# Ant_Robot.net
KiCad netlist of a schematic drawn in Altium Designer
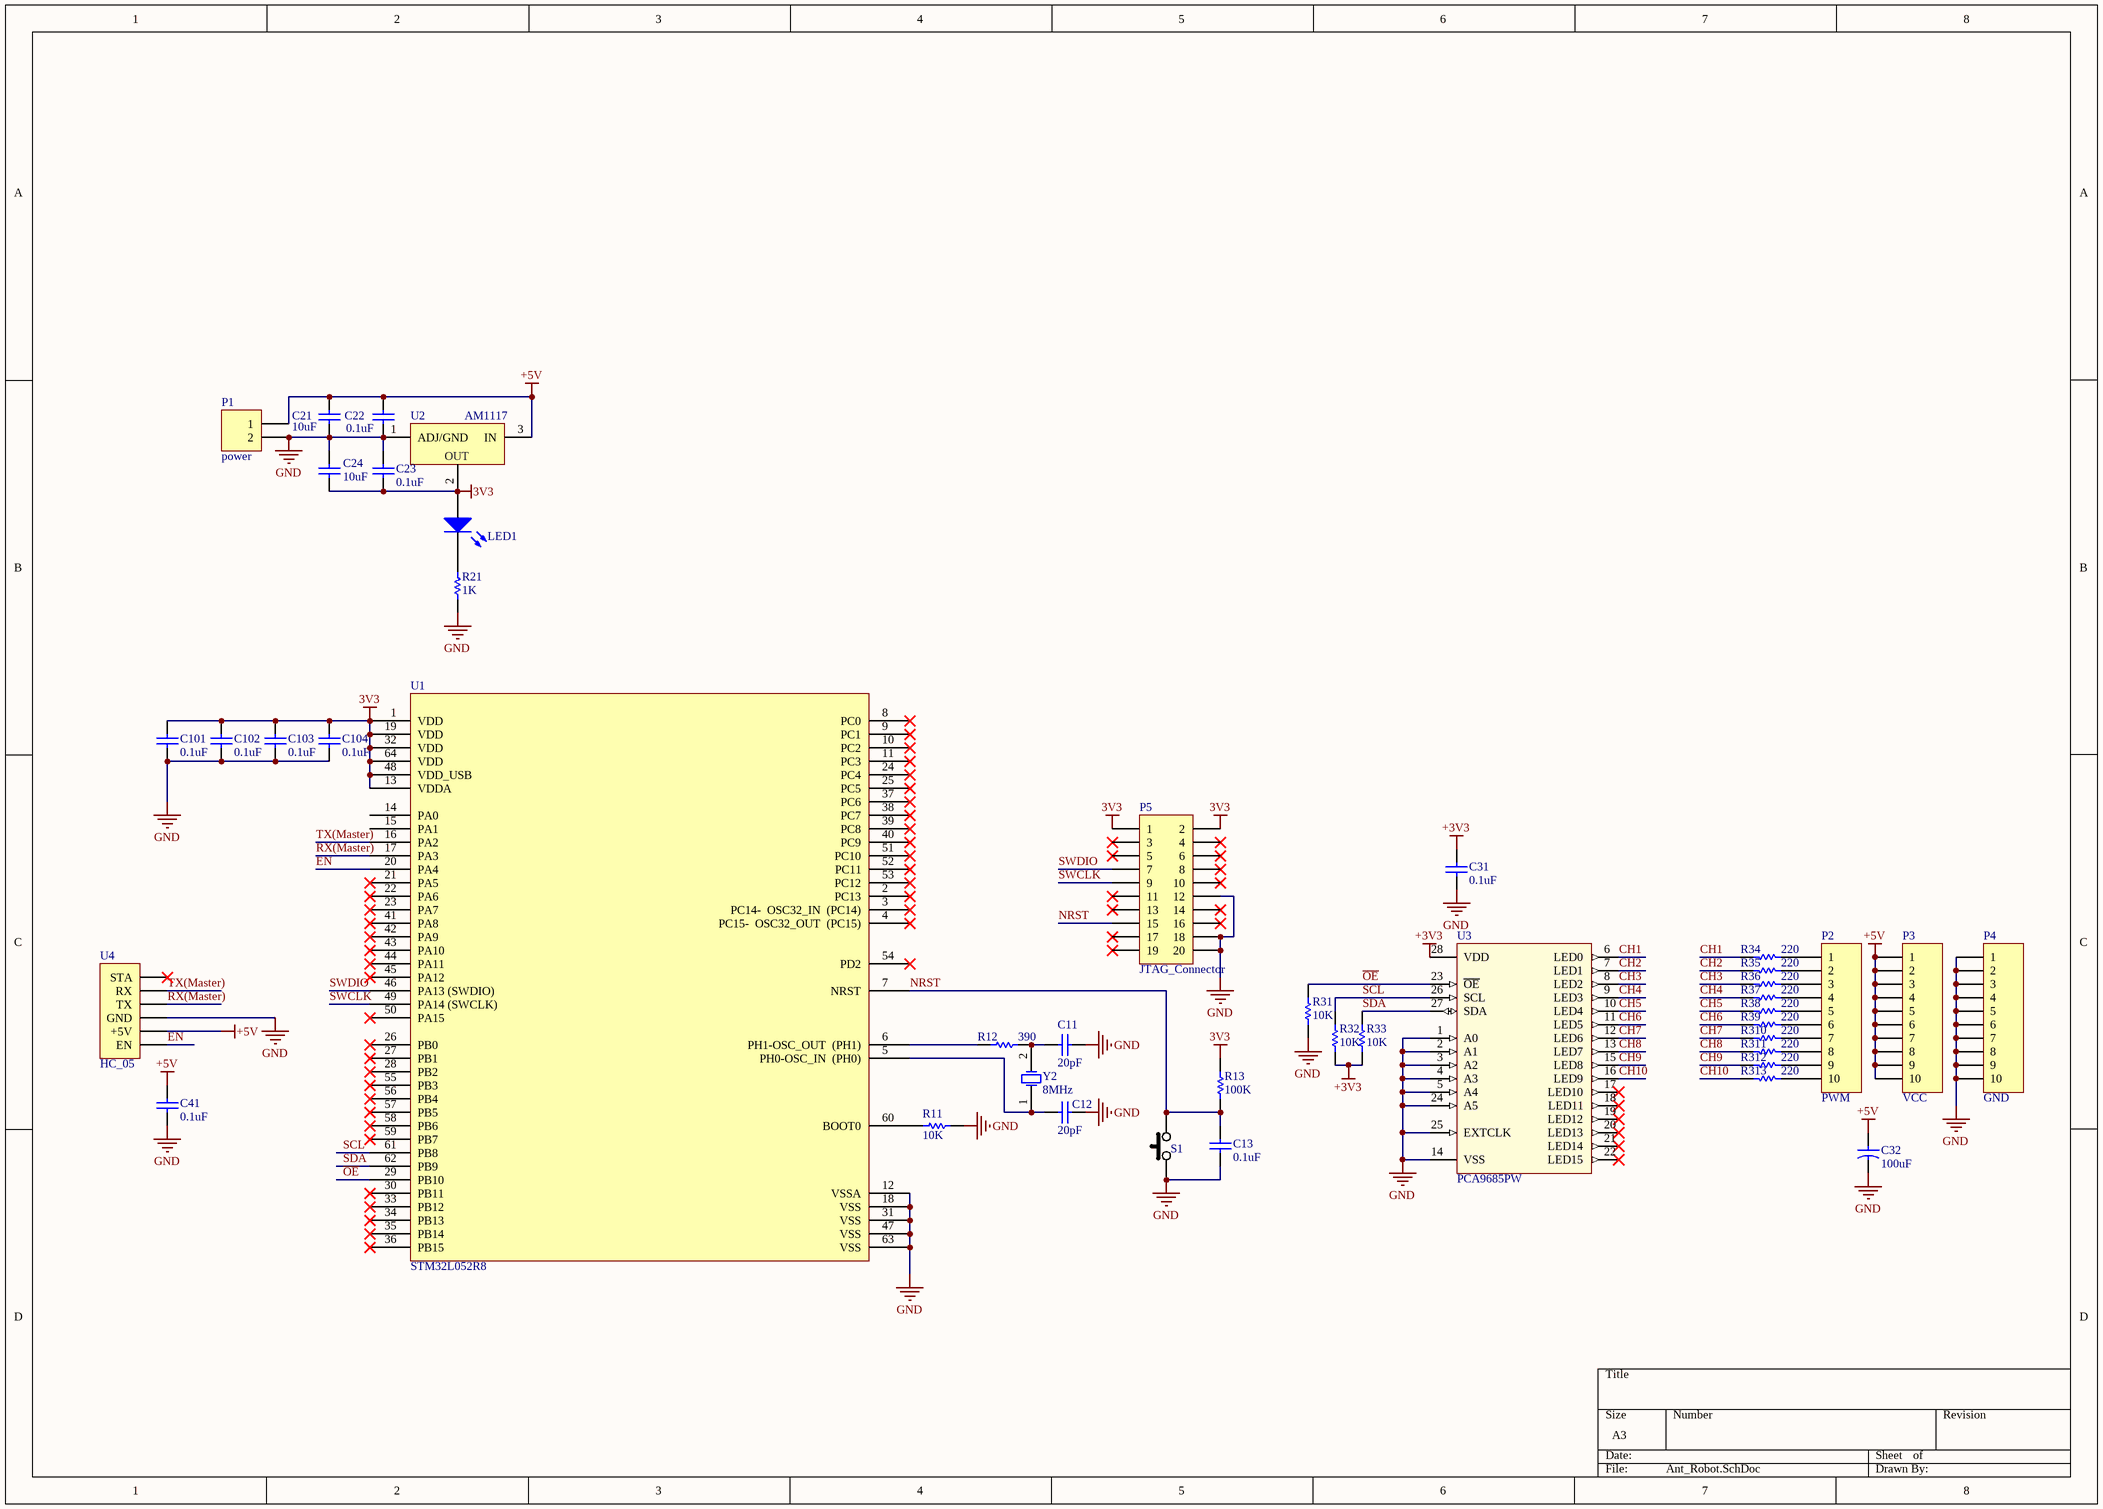
[diagram p0: Ant_Robot.SchDoc]

(export (version "E")
  (design (tool "Eeschema 10.0.6"))
  (components
    (comp (ref "C11") (value "20pF") (footprint "SMD 0805") (libsource (lib "零件庫") (part "C1 陶瓷")))
    (comp (ref "C12") (value "20pF") (footprint "SMD 0805") (libsource (lib "零件庫") (part "C1 陶瓷")))
    (comp (ref "C13") (value "0.1uF") (footprint "SMD 0805") (libsource (lib "零件庫") (part "C1 陶瓷")))
    (comp (ref "C21") (value "10uF") (footprint "SMD 0805") (libsource (lib "零件庫") (part "C1 陶瓷")))
    (comp (ref "C22") (value "0.1uF") (footprint "SMD 0805") (libsource (lib "零件庫") (part "C1 陶瓷")))
    (comp (ref "C23") (value "0.1uF") (footprint "SMD 0805") (libsource (lib "零件庫") (part "C1 陶瓷")))
    (comp (ref "C24") (value "10uF") (footprint "SMD 0805") (libsource (lib "零件庫") (part "C1 陶瓷")))
    (comp (ref "C31") (value "0.1uF") (footprint "SMD 0805") (libsource (lib "零件庫") (part "C1 陶瓷")))
    (comp (ref "C32") (value "100uF") (footprint "C2") (libsource (lib "零件庫") (part "C2 電解")))
    (comp (ref "C41") (value "0.1uF") (footprint "SMD 0805") (libsource (lib "零件庫") (part "C1 陶瓷")))
    (comp (ref "C101") (value "0.1uF") (footprint "SMD 0805") (libsource (lib "零件庫") (part "C1 陶瓷")))
    (comp (ref "C102") (value "0.1uF") (footprint "SMD 0805") (libsource (lib "零件庫") (part "C1 陶瓷")))
    (comp (ref "C103") (value "0.1uF") (footprint "SMD 0805") (libsource (lib "零件庫") (part "C1 陶瓷")))
    (comp (ref "C104") (value "0.1uF") (footprint "SMD 0805") (libsource (lib "零件庫") (part "C1 陶瓷")))
    (comp (ref "LED1") (value "LED") (footprint "SMD 0805") (libsource (lib "零件庫") (part "LED")))
    (comp (ref "P1")
      (value "power")
      (footprint "HDR1X2 - 5mm")
      (description "Header, 2-Pin")
      (fields (field (name "PUBLISHER") "Altium Limited"))
      (libsource (lib "零件庫") (part "Header 2"))
    )
    (comp (ref "P2")
      (value "PWM")
      (footprint "HDR1X10")
      (description "Header, 10-Pin")
      (fields (field (name "PUBLISHER") "Altium Limited"))
      (libsource (lib "Miscellaneous Connectors") (part "Header 10"))
    )
    (comp (ref "P3")
      (value "VCC")
      (footprint "HDR1X10")
      (description "Header, 10-Pin")
      (fields (field (name "PUBLISHER") "Altium Limited"))
      (libsource (lib "Miscellaneous Connectors") (part "Header 10"))
    )
    (comp (ref "P4")
      (value "GND")
      (footprint "HDR1X10")
      (description "Header, 10-Pin")
      (fields (field (name "PUBLISHER") "Altium Limited"))
      (libsource (lib "Miscellaneous Connectors") (part "Header 10"))
    )
    (comp (ref "P5")
      (value "JTAG_Connector")
      (footprint "JTAG_PIN_20")
      (libsource (lib "零件庫") (part "JTAG_Connector"))
    )
    (comp (ref "R11")
      (value "10K")
      (footprint "SMD 0805")
      (description "Resistor")
      (fields (field (name "Comment") "R1") (field (name "PUBLISHER") "Altium Limited"))
      (libsource (lib "零件庫") (part "R1"))
    )
    (comp (ref "R12")
      (value "390")
      (footprint "SMD 0805")
      (description "Resistor")
      (fields (field (name "Comment") "R1") (field (name "PUBLISHER") "Altium Limited"))
      (libsource (lib "零件庫") (part "R1"))
    )
    (comp (ref "R13")
      (value "100K")
      (footprint "SMD 0805")
      (description "Resistor")
      (fields (field (name "Comment") "R1") (field (name "PUBLISHER") "Altium Limited"))
      (libsource (lib "零件庫") (part "R1"))
    )
    (comp (ref "R21")
      (value "1K")
      (footprint "SMD 0805")
      (description "Resistor")
      (fields (field (name "Comment") "R1") (field (name "PUBLISHER") "Altium Limited"))
      (libsource (lib "零件庫") (part "R1"))
    )
    (comp (ref "R31")
      (value "10K")
      (footprint "SMD 0805")
      (description "Resistor")
      (fields (field (name "Comment") "R1") (field (name "PUBLISHER") "Altium Limited"))
      (libsource (lib "零件庫") (part "R1"))
    )
    (comp (ref "R32")
      (value "10K")
      (footprint "SMD 0805")
      (description "Resistor")
      (fields (field (name "Comment") "R1") (field (name "PUBLISHER") "Altium Limited"))
      (libsource (lib "零件庫") (part "R1"))
    )
    (comp (ref "R33")
      (value "10K")
      (footprint "SMD 0805")
      (description "Resistor")
      (fields (field (name "Comment") "R1") (field (name "PUBLISHER") "Altium Limited"))
      (libsource (lib "零件庫") (part "R1"))
    )
    (comp (ref "R34")
      (value "220")
      (footprint "SMD 0805")
      (description "Resistor")
      (fields (field (name "Comment") "R1") (field (name "PUBLISHER") "Altium Limited"))
      (libsource (lib "零件庫") (part "R1"))
    )
    (comp (ref "R35")
      (value "220")
      (footprint "SMD 0805")
      (description "Resistor")
      (fields (field (name "Comment") "R1") (field (name "PUBLISHER") "Altium Limited"))
      (libsource (lib "零件庫") (part "R1"))
    )
    (comp (ref "R36")
      (value "220")
      (footprint "SMD 0805")
      (description "Resistor")
      (fields (field (name "Comment") "R1") (field (name "PUBLISHER") "Altium Limited"))
      (libsource (lib "零件庫") (part "R1"))
    )
    (comp (ref "R37")
      (value "220")
      (footprint "SMD 0805")
      (description "Resistor")
      (fields (field (name "Comment") "R1") (field (name "PUBLISHER") "Altium Limited"))
      (libsource (lib "零件庫") (part "R1"))
    )
    (comp (ref "R38")
      (value "220")
      (footprint "SMD 0805")
      (description "Resistor")
      (fields (field (name "Comment") "R1") (field (name "PUBLISHER") "Altium Limited"))
      (libsource (lib "零件庫") (part "R1"))
    )
    (comp (ref "R39")
      (value "220")
      (footprint "SMD 0805")
      (description "Resistor")
      (fields (field (name "Comment") "R1") (field (name "PUBLISHER") "Altium Limited"))
      (libsource (lib "零件庫") (part "R1"))
    )
    (comp (ref "R310")
      (value "220")
      (footprint "SMD 0805")
      (description "Resistor")
      (fields (field (name "Comment") "R1") (field (name "PUBLISHER") "Altium Limited"))
      (libsource (lib "零件庫") (part "R1"))
    )
    (comp (ref "R311")
      (value "220")
      (footprint "SMD 0805")
      (description "Resistor")
      (fields (field (name "Comment") "R1") (field (name "PUBLISHER") "Altium Limited"))
      (libsource (lib "零件庫") (part "R1"))
    )
    (comp (ref "R312")
      (value "220")
      (footprint "SMD 0805")
      (description "Resistor")
      (fields (field (name "Comment") "R1") (field (name "PUBLISHER") "Altium Limited"))
      (libsource (lib "零件庫") (part "R1"))
    )
    (comp (ref "R313")
      (value "220")
      (footprint "SMD 0805")
      (description "Resistor")
      (fields (field (name "Comment") "R1") (field (name "PUBLISHER") "Altium Limited"))
      (libsource (lib "零件庫") (part "R1"))
    )
    (comp (ref "S1") (value "SW") (footprint "SW") (libsource (lib "零件庫") (part "SW")))
    (comp (ref "U1")
      (value "STM32L052R8")
      (footprint "LQFP64_N")
      (libsource (lib "零件庫") (part "STM32L052R8"))
    )
    (comp (ref "U2") (value "AM1117") (footprint "SOT-223") (libsource (lib "myLib2009") (part "AM1117")))
    (comp (ref "U3")
      (value "PCA9685PW")
      (footprint "TSSOP28")
      (description "16Bits PWM Channel")
      (libsource (lib "零件庫") (part "PCA9685PW"))
    )
    (comp (ref "U4")
      (value "HC_05")
      (footprint "HDR1X6")
      (description "Header, 6-Pin")
      (fields (field (name "PUBLISHER") "Altium Limited"))
      (libsource (lib "零件庫") (part "Header 6"))
    )
    (comp (ref "Y2")
      (value "8MHz")
      (footprint "XTAL4-8")
      (description "Crystal Oscillator")
      (fields (field (name "PUBLISHER") "Altium Limited"))
      (libsource (lib "myLib2009") (part "XTAL"))
    )
  )
  (nets
    (net (code "1") (name "+3V3") (class "Default")
      (node (ref "C31") (pin "2") (pinfunction "2_2") (pintype "passive"))
      (node (ref "R32") (pin "1") (pinfunction "1_1") (pintype "passive"))
      (node (ref "R33") (pin "1") (pinfunction "1_1") (pintype "passive"))
      (node (ref "U3") (pin "28") (pinfunction "VDD_28") (pintype "power_in"))
    )
    (net (code "2") (name "+5V") (class "Default")
      (node (ref "C21") (pin "2") (pinfunction "2_2") (pintype "passive"))
      (node (ref "C22") (pin "2") (pinfunction "2_2") (pintype "passive"))
      (node (ref "C32") (pin "1") (pinfunction "1_1") (pintype "passive"))
      (node (ref "C41") (pin "2") (pinfunction "2_2") (pintype "passive"))
      (node (ref "P1") (pin "1") (pinfunction "1_1") (pintype "passive"))
      (node (ref "P3") (pin "1") (pinfunction "1_1") (pintype "passive"))
      (node (ref "P3") (pin "10") (pinfunction "10_10") (pintype "passive"))
      (node (ref "P3") (pin "2") (pinfunction "2_2") (pintype "passive"))
      (node (ref "P3") (pin "3") (pinfunction "3_3") (pintype "passive"))
      (node (ref "P3") (pin "4") (pinfunction "4_4") (pintype "passive"))
      (node (ref "P3") (pin "5") (pinfunction "5_5") (pintype "passive"))
      (node (ref "P3") (pin "6") (pinfunction "6_6") (pintype "passive"))
      (node (ref "P3") (pin "7") (pinfunction "7_7") (pintype "passive"))
      (node (ref "P3") (pin "8") (pinfunction "8_8") (pintype "passive"))
      (node (ref "P3") (pin "9") (pinfunction "9_9") (pintype "passive"))
      (node (ref "U2") (pin "3") (pinfunction "IN_3") (pintype "power_in"))
      (node (ref "U4") (pin "5") (pinfunction "+5V_5") (pintype "passive"))
    )
    (net (code "3") (name "/CH1") (class "Default")
      (node (ref "R34") (pin "2") (pinfunction "2_2") (pintype "passive"))
      (node (ref "U3") (pin "6") (pinfunction "LED0_6") (pintype "output"))
    )
    (net (code "4") (name "/CH2") (class "Default")
      (node (ref "R35") (pin "2") (pinfunction "2_2") (pintype "passive"))
      (node (ref "U3") (pin "7") (pinfunction "LED1_7") (pintype "output"))
    )
    (net (code "5") (name "/CH3") (class "Default")
      (node (ref "R36") (pin "2") (pinfunction "2_2") (pintype "passive"))
      (node (ref "U3") (pin "8") (pinfunction "LED2_8") (pintype "output"))
    )
    (net (code "6") (name "/CH4") (class "Default")
      (node (ref "R37") (pin "2") (pinfunction "2_2") (pintype "passive"))
      (node (ref "U3") (pin "9") (pinfunction "LED3_9") (pintype "output"))
    )
    (net (code "7") (name "/CH5") (class "Default")
      (node (ref "R38") (pin "2") (pinfunction "2_2") (pintype "passive"))
      (node (ref "U3") (pin "10") (pinfunction "LED4_10") (pintype "output"))
    )
    (net (code "8") (name "/CH6") (class "Default")
      (node (ref "R39") (pin "2") (pinfunction "2_2") (pintype "passive"))
      (node (ref "U3") (pin "11") (pinfunction "LED5_11") (pintype "output"))
    )
    (net (code "9") (name "/CH7") (class "Default")
      (node (ref "R310") (pin "2") (pinfunction "2_2") (pintype "passive"))
      (node (ref "U3") (pin "12") (pinfunction "LED6_12") (pintype "output"))
    )
    (net (code "10") (name "/CH8") (class "Default")
      (node (ref "R311") (pin "2") (pinfunction "2_2") (pintype "passive"))
      (node (ref "U3") (pin "13") (pinfunction "LED7_13") (pintype "output"))
    )
    (net (code "11") (name "/CH9") (class "Default")
      (node (ref "R312") (pin "2") (pinfunction "2_2") (pintype "passive"))
      (node (ref "U3") (pin "15") (pinfunction "LED8_15") (pintype "output"))
    )
    (net (code "12") (name "/CH10") (class "Default")
      (node (ref "R313") (pin "2") (pinfunction "2_2") (pintype "passive"))
      (node (ref "U3") (pin "16") (pinfunction "LED9_16") (pintype "output"))
    )
    (net (code "13") (name "/EN") (class "Default")
      (node (ref "U1") (pin "20") (pinfunction "PA4_20") (pintype "passive"))
      (node (ref "U4") (pin "6") (pinfunction "EN_6") (pintype "passive"))
    )
    (net (code "14") (name "/NRST") (class "Default")
      (node (ref "C13") (pin "1") (pinfunction "1_1") (pintype "passive"))
      (node (ref "P5") (pin "15") (pinfunction "15_15") (pintype "passive"))
      (node (ref "R13") (pin "1") (pinfunction "1_1") (pintype "passive"))
      (node (ref "S1") (pin "1") (pinfunction "1_1") (pintype "passive"))
      (node (ref "U1") (pin "7") (pinfunction "NRST_7") (pintype "passive"))
    )
    (net (code "15") (name "/RX(Master)") (class "Default")
      (node (ref "U1") (pin "17") (pinfunction "PA3_17") (pintype "passive"))
      (node (ref "U4") (pin "3") (pinfunction "TX_3") (pintype "passive"))
    )
    (net (code "16") (name "/SCL") (class "Default")
      (node (ref "R32") (pin "2") (pinfunction "2_2") (pintype "passive"))
      (node (ref "U1") (pin "61") (pinfunction "PB8_61") (pintype "passive"))
      (node (ref "U3") (pin "26") (pinfunction "SCL_26") (pintype "input"))
    )
    (net (code "17") (name "/SDA") (class "Default")
      (node (ref "R33") (pin "2") (pinfunction "2_2") (pintype "passive"))
      (node (ref "U1") (pin "62") (pinfunction "PB9_62") (pintype "passive"))
      (node (ref "U3") (pin "27") (pinfunction "SDA_27") (pintype "bidirectional"))
    )
    (net (code "18") (name "/SWCLK") (class "Default")
      (node (ref "P5") (pin "9") (pinfunction "9_9") (pintype "passive"))
      (node (ref "U1") (pin "49") (pinfunction "PA14_(SWCLK)_49") (pintype "passive"))
    )
    (net (code "19") (name "/SWDIO") (class "Default")
      (node (ref "P5") (pin "7") (pinfunction "7_7") (pintype "passive"))
      (node (ref "U1") (pin "46") (pinfunction "PA13_(SWDIO)_46") (pintype "passive"))
    )
    (net (code "20") (name "/TX(Master)") (class "Default")
      (node (ref "U1") (pin "16") (pinfunction "PA2_16") (pintype "passive"))
      (node (ref "U4") (pin "2") (pinfunction "RX_2") (pintype "passive"))
    )
    (net (code "21") (name "/~{OE}") (class "Default")
      (node (ref "R31") (pin "2") (pinfunction "2_2") (pintype "passive"))
      (node (ref "U1") (pin "29") (pinfunction "PB10_29") (pintype "passive"))
      (node (ref "U3") (pin "23") (pinfunction "~{OE}_23") (pintype "input"))
    )
    (net (code "22") (name "3V3") (class "Default")
      (node (ref "C101") (pin "2") (pinfunction "2_2") (pintype "passive"))
      (node (ref "C102") (pin "2") (pinfunction "2_2") (pintype "passive"))
      (node (ref "C103") (pin "2") (pinfunction "2_2") (pintype "passive"))
      (node (ref "C104") (pin "2") (pinfunction "2_2") (pintype "passive"))
      (node (ref "C23") (pin "1") (pinfunction "1_1") (pintype "passive"))
      (node (ref "C24") (pin "1") (pinfunction "1_1") (pintype "passive"))
      (node (ref "LED1") (pin "1") (pinfunction "A_1") (pintype "passive"))
      (node (ref "P5") (pin "1") (pinfunction "1_1") (pintype "passive"))
      (node (ref "P5") (pin "2") (pinfunction "2_2") (pintype "passive"))
      (node (ref "R13") (pin "2") (pinfunction "2_2") (pintype "passive"))
      (node (ref "U1") (pin "1") (pinfunction "VDD_1") (pintype "passive"))
      (node (ref "U1") (pin "13") (pinfunction "VDDA_13") (pintype "passive"))
      (node (ref "U1") (pin "19") (pinfunction "VDD_19") (pintype "passive"))
      (node (ref "U1") (pin "32") (pinfunction "VDD_32") (pintype "passive"))
      (node (ref "U1") (pin "48") (pinfunction "VDD_USB_48") (pintype "passive"))
      (node (ref "U1") (pin "64") (pinfunction "VDD_64") (pintype "passive"))
      (node (ref "U2") (pin "2") (pinfunction "OUT_2") (pintype "power_in"))
    )
    (net (code "23") (name "GND") (class "Default")
      (node (ref "C101") (pin "1") (pinfunction "1_1") (pintype "passive"))
      (node (ref "C102") (pin "1") (pinfunction "1_1") (pintype "passive"))
      (node (ref "C103") (pin "1") (pinfunction "1_1") (pintype "passive"))
      (node (ref "C104") (pin "1") (pinfunction "1_1") (pintype "passive"))
      (node (ref "C11") (pin "1") (pinfunction "1_1") (pintype "passive"))
      (node (ref "C12") (pin "1") (pinfunction "1_1") (pintype "passive"))
      (node (ref "C13") (pin "2") (pinfunction "2_2") (pintype "passive"))
      (node (ref "C21") (pin "1") (pinfunction "1_1") (pintype "passive"))
      (node (ref "C22") (pin "1") (pinfunction "1_1") (pintype "passive"))
      (node (ref "C23") (pin "2") (pinfunction "2_2") (pintype "passive"))
      (node (ref "C24") (pin "2") (pinfunction "2_2") (pintype "passive"))
      (node (ref "C31") (pin "1") (pinfunction "1_1") (pintype "passive"))
      (node (ref "C32") (pin "2") (pinfunction "2_2") (pintype "passive"))
      (node (ref "C41") (pin "1") (pinfunction "1_1") (pintype "passive"))
      (node (ref "P1") (pin "2") (pinfunction "2_2") (pintype "passive"))
      (node (ref "P4") (pin "1") (pinfunction "1_1") (pintype "passive"))
      (node (ref "P4") (pin "10") (pinfunction "10_10") (pintype "passive"))
      (node (ref "P4") (pin "2") (pinfunction "2_2") (pintype "passive"))
      (node (ref "P4") (pin "3") (pinfunction "3_3") (pintype "passive"))
      (node (ref "P4") (pin "4") (pinfunction "4_4") (pintype "passive"))
      (node (ref "P4") (pin "5") (pinfunction "5_5") (pintype "passive"))
      (node (ref "P4") (pin "6") (pinfunction "6_6") (pintype "passive"))
      (node (ref "P4") (pin "7") (pinfunction "7_7") (pintype "passive"))
      (node (ref "P4") (pin "8") (pinfunction "8_8") (pintype "passive"))
      (node (ref "P4") (pin "9") (pinfunction "9_9") (pintype "passive"))
      (node (ref "P5") (pin "12") (pinfunction "12_12") (pintype "passive"))
      (node (ref "P5") (pin "18") (pinfunction "18_18") (pintype "passive"))
      (node (ref "P5") (pin "20") (pinfunction "20_20") (pintype "passive"))
      (node (ref "R11") (pin "2") (pinfunction "2_2") (pintype "passive"))
      (node (ref "R21") (pin "1") (pinfunction "1_1") (pintype "passive"))
      (node (ref "R31") (pin "1") (pinfunction "1_1") (pintype "passive"))
      (node (ref "S1") (pin "2") (pinfunction "2_2") (pintype "passive"))
      (node (ref "U1") (pin "12") (pinfunction "VSSA_12") (pintype "passive"))
      (node (ref "U1") (pin "18") (pinfunction "VSS_18") (pintype "passive"))
      (node (ref "U1") (pin "31") (pinfunction "VSS_31") (pintype "passive"))
      (node (ref "U1") (pin "47") (pinfunction "VSS_47") (pintype "passive"))
      (node (ref "U1") (pin "63") (pinfunction "VSS_63") (pintype "passive"))
      (node (ref "U2") (pin "1") (pinfunction "ADJ/GND_1") (pintype "power_in"))
      (node (ref "U3") (pin "1") (pinfunction "A0_1") (pintype "input"))
      (node (ref "U3") (pin "14") (pinfunction "VSS_14") (pintype "passive"))
      (node (ref "U3") (pin "2") (pinfunction "A1_2") (pintype "input"))
      (node (ref "U3") (pin "24") (pinfunction "A5_24") (pintype "input"))
      (node (ref "U3") (pin "25") (pinfunction "EXTCLK_25") (pintype "input"))
      (node (ref "U3") (pin "3") (pinfunction "A2_3") (pintype "input"))
      (node (ref "U3") (pin "4") (pinfunction "A3_4") (pintype "input"))
      (node (ref "U3") (pin "5") (pinfunction "A4_5") (pintype "input"))
      (node (ref "U4") (pin "4") (pinfunction "GND_4") (pintype "passive"))
    )
    (net (code "24") (name "Net-(LED1-K)") (class "Default")
      (node (ref "LED1") (pin "2") (pinfunction "K_2") (pintype "passive"))
      (node (ref "R21") (pin "2") (pinfunction "2_2") (pintype "passive"))
    )
    (net (code "25") (name "Net-(P2-Pad1)") (class "Default")
      (node (ref "P2") (pin "1") (pinfunction "1_1") (pintype "passive"))
      (node (ref "R34") (pin "1") (pinfunction "1_1") (pintype "passive"))
    )
    (net (code "26") (name "Net-(P2-Pad2)") (class "Default")
      (node (ref "P2") (pin "2") (pinfunction "2_2") (pintype "passive"))
      (node (ref "R35") (pin "1") (pinfunction "1_1") (pintype "passive"))
    )
    (net (code "27") (name "Net-(P2-Pad3)") (class "Default")
      (node (ref "P2") (pin "3") (pinfunction "3_3") (pintype "passive"))
      (node (ref "R36") (pin "1") (pinfunction "1_1") (pintype "passive"))
    )
    (net (code "28") (name "Net-(P2-Pad4)") (class "Default")
      (node (ref "P2") (pin "4") (pinfunction "4_4") (pintype "passive"))
      (node (ref "R37") (pin "1") (pinfunction "1_1") (pintype "passive"))
    )
    (net (code "29") (name "Net-(P2-Pad5)") (class "Default")
      (node (ref "P2") (pin "5") (pinfunction "5_5") (pintype "passive"))
      (node (ref "R38") (pin "1") (pinfunction "1_1") (pintype "passive"))
    )
    (net (code "30") (name "Net-(P2-Pad6)") (class "Default")
      (node (ref "P2") (pin "6") (pinfunction "6_6") (pintype "passive"))
      (node (ref "R39") (pin "1") (pinfunction "1_1") (pintype "passive"))
    )
    (net (code "31") (name "Net-(P2-Pad7)") (class "Default")
      (node (ref "P2") (pin "7") (pinfunction "7_7") (pintype "passive"))
      (node (ref "R310") (pin "1") (pinfunction "1_1") (pintype "passive"))
    )
    (net (code "32") (name "Net-(P2-Pad8)") (class "Default")
      (node (ref "P2") (pin "8") (pinfunction "8_8") (pintype "passive"))
      (node (ref "R311") (pin "1") (pinfunction "1_1") (pintype "passive"))
    )
    (net (code "33") (name "Net-(P2-Pad9)") (class "Default")
      (node (ref "P2") (pin "9") (pinfunction "9_9") (pintype "passive"))
      (node (ref "R312") (pin "1") (pinfunction "1_1") (pintype "passive"))
    )
    (net (code "34") (name "Net-(P2-Pad10)") (class "Default")
      (node (ref "P2") (pin "10") (pinfunction "10_10") (pintype "passive"))
      (node (ref "R313") (pin "1") (pinfunction "1_1") (pintype "passive"))
    )
    (net (code "35") (name "Net-(U1-BOOT0)") (class "Default")
      (node (ref "R11") (pin "1") (pinfunction "1_1") (pintype "passive"))
      (node (ref "U1") (pin "60") (pinfunction "BOOT0_60") (pintype "passive"))
    )
    (net (code "36") (name "Net-(U1-PH0-OSC_IN__(PH0))") (class "Default")
      (node (ref "C12") (pin "2") (pinfunction "2_2") (pintype "passive"))
      (node (ref "U1") (pin "5") (pinfunction "PH0-OSC_IN__(PH0)_5") (pintype "passive"))
      (node (ref "Y2") (pin "1") (pinfunction "OSC1_1") (pintype "passive"))
    )
    (net (code "37") (name "Net-(U1-PH1-OSC_OUT__(PH1))") (class "Default")
      (node (ref "R12") (pin "1") (pinfunction "1_1") (pintype "passive"))
      (node (ref "U1") (pin "6") (pinfunction "PH1-OSC_OUT__(PH1)_6") (pintype "passive"))
    )
    (net (code "38") (name "Net-(Y2-OSC2)") (class "Default")
      (node (ref "C11") (pin "2") (pinfunction "2_2") (pintype "passive"))
      (node (ref "R12") (pin "2") (pinfunction "2_2") (pintype "passive"))
      (node (ref "Y2") (pin "2") (pinfunction "OSC2_2") (pintype "passive"))
    )
    (net (code "39") (name "unconnected-(P5-Pad3)") (class "Default")
      (node (ref "P5") (pin "3") (pinfunction "3_3") (pintype "passive+no_connect"))
    )
    (net (code "40") (name "unconnected-(P5-Pad4)") (class "Default")
      (node (ref "P5") (pin "4") (pinfunction "4_4") (pintype "passive+no_connect"))
    )
    (net (code "41") (name "unconnected-(P5-Pad5)") (class "Default")
      (node (ref "P5") (pin "5") (pinfunction "5_5") (pintype "passive+no_connect"))
    )
    (net (code "42") (name "unconnected-(P5-Pad6)") (class "Default")
      (node (ref "P5") (pin "6") (pinfunction "6_6") (pintype "passive+no_connect"))
    )
    (net (code "43") (name "unconnected-(P5-Pad8)") (class "Default")
      (node (ref "P5") (pin "8") (pinfunction "8_8") (pintype "passive+no_connect"))
    )
    (net (code "44") (name "unconnected-(P5-Pad10)") (class "Default")
      (node (ref "P5") (pin "10") (pinfunction "10_10") (pintype "passive+no_connect"))
    )
    (net (code "45") (name "unconnected-(P5-Pad11)") (class "Default")
      (node (ref "P5") (pin "11") (pinfunction "11_11") (pintype "passive+no_connect"))
    )
    (net (code "46") (name "unconnected-(P5-Pad13)") (class "Default")
      (node (ref "P5") (pin "13") (pinfunction "13_13") (pintype "passive+no_connect"))
    )
    (net (code "47") (name "unconnected-(P5-Pad14)") (class "Default")
      (node (ref "P5") (pin "14") (pinfunction "14_14") (pintype "passive+no_connect"))
    )
    (net (code "48") (name "unconnected-(P5-Pad16)") (class "Default")
      (node (ref "P5") (pin "16") (pinfunction "16_16") (pintype "passive+no_connect"))
    )
    (net (code "49") (name "unconnected-(P5-Pad17)") (class "Default")
      (node (ref "P5") (pin "17") (pinfunction "17_17") (pintype "passive+no_connect"))
    )
    (net (code "50") (name "unconnected-(P5-Pad19)") (class "Default")
      (node (ref "P5") (pin "19") (pinfunction "19_19") (pintype "passive+no_connect"))
    )
    (net (code "51") (name "unconnected-(U1-PA0-Pad14)") (class "Default")
      (node (ref "U1") (pin "14") (pinfunction "PA0_14") (pintype "passive"))
    )
    (net (code "52") (name "unconnected-(U1-PA1-Pad15)") (class "Default")
      (node (ref "U1") (pin "15") (pinfunction "PA1_15") (pintype "passive"))
    )
    (net (code "53") (name "unconnected-(U1-PA5-Pad21)") (class "Default")
      (node (ref "U1") (pin "21") (pinfunction "PA5_21") (pintype "passive+no_connect"))
    )
    (net (code "54") (name "unconnected-(U1-PA6-Pad22)") (class "Default")
      (node (ref "U1") (pin "22") (pinfunction "PA6_22") (pintype "passive+no_connect"))
    )
    (net (code "55") (name "unconnected-(U1-PA7-Pad23)") (class "Default")
      (node (ref "U1") (pin "23") (pinfunction "PA7_23") (pintype "passive+no_connect"))
    )
    (net (code "56") (name "unconnected-(U1-PA8-Pad41)") (class "Default")
      (node (ref "U1") (pin "41") (pinfunction "PA8_41") (pintype "passive+no_connect"))
    )
    (net (code "57") (name "unconnected-(U1-PA9-Pad42)") (class "Default")
      (node (ref "U1") (pin "42") (pinfunction "PA9_42") (pintype "passive+no_connect"))
    )
    (net (code "58") (name "unconnected-(U1-PA10-Pad43)") (class "Default")
      (node (ref "U1") (pin "43") (pinfunction "PA10_43") (pintype "passive+no_connect"))
    )
    (net (code "59") (name "unconnected-(U1-PA11-Pad44)") (class "Default")
      (node (ref "U1") (pin "44") (pinfunction "PA11_44") (pintype "passive+no_connect"))
    )
    (net (code "60") (name "unconnected-(U1-PA12-Pad45)") (class "Default")
      (node (ref "U1") (pin "45") (pinfunction "PA12_45") (pintype "passive+no_connect"))
    )
    (net (code "61") (name "unconnected-(U1-PA15-Pad50)") (class "Default")
      (node (ref "U1") (pin "50") (pinfunction "PA15_50") (pintype "passive+no_connect"))
    )
    (net (code "62") (name "unconnected-(U1-PB0-Pad26)") (class "Default")
      (node (ref "U1") (pin "26") (pinfunction "PB0_26") (pintype "passive+no_connect"))
    )
    (net (code "63") (name "unconnected-(U1-PB1-Pad27)") (class "Default")
      (node (ref "U1") (pin "27") (pinfunction "PB1_27") (pintype "passive+no_connect"))
    )
    (net (code "64") (name "unconnected-(U1-PB2-Pad28)") (class "Default")
      (node (ref "U1") (pin "28") (pinfunction "PB2_28") (pintype "passive+no_connect"))
    )
    (net (code "65") (name "unconnected-(U1-PB3-Pad55)") (class "Default")
      (node (ref "U1") (pin "55") (pinfunction "PB3_55") (pintype "passive+no_connect"))
    )
    (net (code "66") (name "unconnected-(U1-PB4-Pad56)") (class "Default")
      (node (ref "U1") (pin "56") (pinfunction "PB4_56") (pintype "passive+no_connect"))
    )
    (net (code "67") (name "unconnected-(U1-PB5-Pad57)") (class "Default")
      (node (ref "U1") (pin "57") (pinfunction "PB5_57") (pintype "passive+no_connect"))
    )
    (net (code "68") (name "unconnected-(U1-PB6-Pad58)") (class "Default")
      (node (ref "U1") (pin "58") (pinfunction "PB6_58") (pintype "passive+no_connect"))
    )
    (net (code "69") (name "unconnected-(U1-PB7-Pad59)") (class "Default")
      (node (ref "U1") (pin "59") (pinfunction "PB7_59") (pintype "passive+no_connect"))
    )
    (net (code "70") (name "unconnected-(U1-PB11-Pad30)") (class "Default")
      (node (ref "U1") (pin "30") (pinfunction "PB11_30") (pintype "passive+no_connect"))
    )
    (net (code "71") (name "unconnected-(U1-PB12-Pad33)") (class "Default")
      (node (ref "U1") (pin "33") (pinfunction "PB12_33") (pintype "passive+no_connect"))
    )
    (net (code "72") (name "unconnected-(U1-PB13-Pad34)") (class "Default")
      (node (ref "U1") (pin "34") (pinfunction "PB13_34") (pintype "passive+no_connect"))
    )
    (net (code "73") (name "unconnected-(U1-PB14-Pad35)") (class "Default")
      (node (ref "U1") (pin "35") (pinfunction "PB14_35") (pintype "passive+no_connect"))
    )
    (net (code "74") (name "unconnected-(U1-PB15-Pad36)") (class "Default")
      (node (ref "U1") (pin "36") (pinfunction "PB15_36") (pintype "passive+no_connect"))
    )
    (net (code "75") (name "unconnected-(U1-PC0-Pad8)") (class "Default")
      (node (ref "U1") (pin "8") (pinfunction "PC0_8") (pintype "passive+no_connect"))
    )
    (net (code "76") (name "unconnected-(U1-PC1-Pad9)") (class "Default")
      (node (ref "U1") (pin "9") (pinfunction "PC1_9") (pintype "passive+no_connect"))
    )
    (net (code "77") (name "unconnected-(U1-PC2-Pad10)") (class "Default")
      (node (ref "U1") (pin "10") (pinfunction "PC2_10") (pintype "passive+no_connect"))
    )
    (net (code "78") (name "unconnected-(U1-PC3-Pad11)") (class "Default")
      (node (ref "U1") (pin "11") (pinfunction "PC3_11") (pintype "passive+no_connect"))
    )
    (net (code "79") (name "unconnected-(U1-PC4-Pad24)") (class "Default")
      (node (ref "U1") (pin "24") (pinfunction "PC4_24") (pintype "passive+no_connect"))
    )
    (net (code "80") (name "unconnected-(U1-PC5-Pad25)") (class "Default")
      (node (ref "U1") (pin "25") (pinfunction "PC5_25") (pintype "passive+no_connect"))
    )
    (net (code "81") (name "unconnected-(U1-PC6-Pad37)") (class "Default")
      (node (ref "U1") (pin "37") (pinfunction "PC6_37") (pintype "passive+no_connect"))
    )
    (net (code "82") (name "unconnected-(U1-PC7-Pad38)") (class "Default")
      (node (ref "U1") (pin "38") (pinfunction "PC7_38") (pintype "passive+no_connect"))
    )
    (net (code "83") (name "unconnected-(U1-PC8-Pad39)") (class "Default")
      (node (ref "U1") (pin "39") (pinfunction "PC8_39") (pintype "passive+no_connect"))
    )
    (net (code "84") (name "unconnected-(U1-PC9-Pad40)") (class "Default")
      (node (ref "U1") (pin "40") (pinfunction "PC9_40") (pintype "passive+no_connect"))
    )
    (net (code "85") (name "unconnected-(U1-PC10-Pad51)") (class "Default")
      (node (ref "U1") (pin "51") (pinfunction "PC10_51") (pintype "passive+no_connect"))
    )
    (net (code "86") (name "unconnected-(U1-PC11-Pad52)") (class "Default")
      (node (ref "U1") (pin "52") (pinfunction "PC11_52") (pintype "passive+no_connect"))
    )
    (net (code "87") (name "unconnected-(U1-PC12-Pad53)") (class "Default")
      (node (ref "U1") (pin "53") (pinfunction "PC12_53") (pintype "passive+no_connect"))
    )
    (net (code "88") (name "unconnected-(U1-PC13-Pad2)") (class "Default")
      (node (ref "U1") (pin "2") (pinfunction "PC13_2") (pintype "passive+no_connect"))
    )
    (net (code "89") (name "unconnected-(U1-PC14-__OSC32_IN__(PC14)-Pad3)") (class "Default")
      (node (ref "U1") (pin "3") (pinfunction "PC14-__OSC32_IN__(PC14)_3") (pintype "passive+no_connect"))
    )
    (net (code "90") (name "unconnected-(U1-PC15-__OSC32_OUT__(PC15)-Pad4)") (class "Default")
      (node (ref "U1") (pin "4") (pinfunction "PC15-__OSC32_OUT__(PC15)_4") (pintype "passive+no_connect"))
    )
    (net (code "91") (name "unconnected-(U1-PD2-Pad54)") (class "Default")
      (node (ref "U1") (pin "54") (pinfunction "PD2_54") (pintype "passive+no_connect"))
    )
    (net (code "92") (name "unconnected-(U3-LED10-Pad17)") (class "Default")
      (node (ref "U3") (pin "17") (pinfunction "LED10_17") (pintype "output+no_connect"))
    )
    (net (code "93") (name "unconnected-(U3-LED11-Pad18)") (class "Default")
      (node (ref "U3") (pin "18") (pinfunction "LED11_18") (pintype "output+no_connect"))
    )
    (net (code "94") (name "unconnected-(U3-LED12-Pad19)") (class "Default")
      (node (ref "U3") (pin "19") (pinfunction "LED12_19") (pintype "output+no_connect"))
    )
    (net (code "95") (name "unconnected-(U3-LED13-Pad20)") (class "Default")
      (node (ref "U3") (pin "20") (pinfunction "LED13_20") (pintype "output+no_connect"))
    )
    (net (code "96") (name "unconnected-(U3-LED14-Pad21)") (class "Default")
      (node (ref "U3") (pin "21") (pinfunction "LED14_21") (pintype "output+no_connect"))
    )
    (net (code "97") (name "unconnected-(U3-LED15-Pad22)") (class "Default")
      (node (ref "U3") (pin "22") (pinfunction "LED15_22") (pintype "output+no_connect"))
    )
    (net (code "98") (name "unconnected-(U4-STA-Pad1)") (class "Default")
      (node (ref "U4") (pin "1") (pinfunction "STA_1") (pintype "passive+no_connect"))
    )
  )
)
